# IQ_AMP.net
KiCad netlist of a schematic drawn in Altium Designer
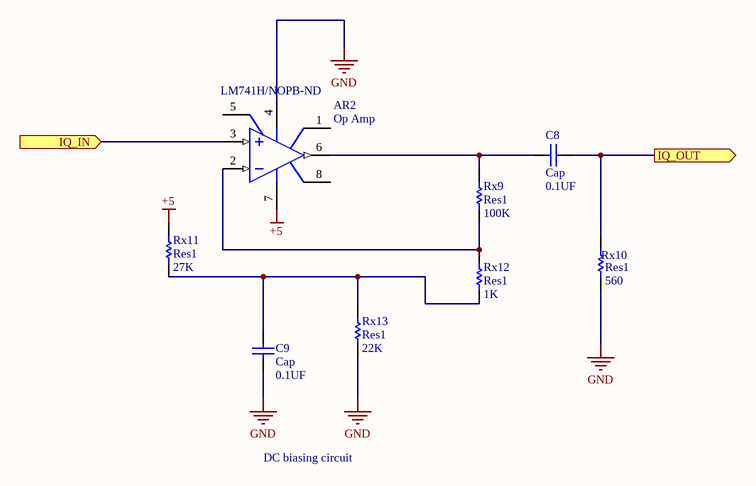
[diagram p0: IQ_AMP.SchDoc]

(export (version "E")
  (design (tool "Eeschema 10.0.6"))
  (components
    (comp (ref "AR2")
      (value "Op Amp")
      (footprint "H-08A")
      (description "FET Operational Amplifier")
      (fields
        (field (name "SUPPLIER PART NUMBER 1") "LM741H/NOPB-ND")
        (field (name "PUBLISHER") "Altium Limited")
      )
      (libsource (lib "Miscellaneous Devices") (part "Op Amp"))
    )
    (comp (ref "C8")
      (value "Cap")
      (footprint "1206")
      (description "Capacitor")
      (fields
        (field (name "ALTIUM_VALUE") "0.1UF")
        (field (name "MANUFACTURER PART NUMBER") "885012208087")
        (field (name "PUBLISHER") "Altium Limited")
      )
      (libsource (lib "ECE295-Capacitors-SMT") (part "CAP CER 0.1UF 50V X7R 1206"))
    )
    (comp (ref "C9")
      (value "Cap")
      (footprint "1206")
      (description "Capacitor")
      (fields
        (field (name "ALTIUM_VALUE") "0.1UF")
        (field (name "MANUFACTURER PART NUMBER") "885012208087")
        (field (name "PUBLISHER") "Altium Limited")
      )
      (libsource (lib "ECE295-Capacitors-SMT") (part "CAP CER 0.1UF 50V X7R 1206"))
    )
    (comp (ref "Rx9")
      (value "Res1")
      (footprint "AXIAL-0.1-RES")
      (description "Resistor")
      (fields
        (field (name "ALTIUM_VALUE") "100K")
        (field (name "MANUFACTURER PART NUMBER") "CFR-25JB-52-100K")
        (field (name "TOLERANCE") "0.05")
        (field (name "PUBLISHER") "Altium Limited")
      )
      (libsource (lib "ECE295-Resistors-TH") (part "RES 100K OHM 5% 1/4W AXIAL"))
    )
    (comp (ref "Rx10")
      (value "Res1")
      (footprint "AXIAL-0.1-RES")
      (description "Resistor")
      (fields
        (field (name "ALTIUM_VALUE") "560")
        (field (name "MANUFACTURER PART NUMBER") "CFR-25JB-52-560R")
        (field (name "TOLERANCE") "0.05")
        (field (name "PUBLISHER") "Altium Limited")
      )
      (libsource (lib "ECE295-Resistors-TH") (part "RES 560 OHM 5% 1/4W AXIAL"))
    )
    (comp (ref "Rx11")
      (value "Res1")
      (footprint "AXIAL-0.1-RES")
      (description "Resistor")
      (fields
        (field (name "ALTIUM_VALUE") "27K")
        (field (name "MANUFACTURER PART NUMBER") "CFR-25JB-52-27K")
        (field (name "TOLERANCE") "0.05")
        (field (name "PUBLISHER") "Altium Limited")
      )
      (libsource (lib "ECE295-Resistors-TH") (part "RES 27K OHM 5% 1/4W AXIAL"))
    )
    (comp (ref "Rx12")
      (value "Res1")
      (footprint "AXIAL-0.1-RES")
      (description "Resistor")
      (fields
        (field (name "MANUFACTURER PART NUMBER") "CFR-25JB-52-1K")
        (field (name "TOLERANCE") "0.05")
        (field (name "ALTIUM_VALUE") "1K")
        (field (name "PUBLISHER") "Altium Limited")
      )
      (libsource (lib "ECE295-Resistors-TH") (part "RES 1K OHM 5% 1/4W AXIAL"))
    )
    (comp (ref "Rx13")
      (value "Res1")
      (footprint "AXIAL-0.1-RES")
      (description "Resistor")
      (fields
        (field (name "ALTIUM_VALUE") "22K")
        (field (name "MANUFACTURER PART NUMBER") "CFR-25JB-52-22K")
        (field (name "TOLERANCE") "0.05")
        (field (name "PUBLISHER") "Altium Limited")
      )
      (libsource (lib "ECE295-Resistors-TH") (part "RES 22K OHM 5% 1/4W AXIAL"))
    )
  )
  (nets
    (net (code "1") (name "+5") (class "Default")
      (node (ref "AR2") (pin "7") (pinfunction "V+_7") (pintype "power_in"))
      (node (ref "Rx11") (pin "2") (pinfunction "2_2") (pintype "passive"))
    )
    (net (code "2") (name "/IQ_IN") (class "Default")
      (node (ref "AR2") (pin "3") (pinfunction "IN+_3") (pintype "input"))
    )
    (net (code "3") (name "/IQ_OUT") (class "Default")
      (node (ref "C8") (pin "2") (pinfunction "2_2") (pintype "passive"))
      (node (ref "Rx10") (pin "2") (pinfunction "2_2") (pintype "passive"))
    )
    (net (code "4") (name "GND") (class "Default")
      (node (ref "AR2") (pin "4") (pinfunction "V-_4") (pintype "power_in"))
      (node (ref "C9") (pin "1") (pinfunction "1_1") (pintype "passive"))
      (node (ref "Rx10") (pin "1") (pinfunction "1_1") (pintype "passive"))
      (node (ref "Rx13") (pin "1") (pinfunction "1_1") (pintype "passive"))
    )
    (net (code "5") (name "Net-(AR2-IN-)") (class "Default")
      (node (ref "AR2") (pin "2") (pinfunction "IN-_2") (pintype "input"))
      (node (ref "Rx12") (pin "2") (pinfunction "2_2") (pintype "passive"))
      (node (ref "Rx9") (pin "1") (pinfunction "1_1") (pintype "passive"))
    )
    (net (code "6") (name "Net-(AR2-OUT)") (class "Default")
      (node (ref "AR2") (pin "6") (pinfunction "OUT_6") (pintype "output"))
      (node (ref "C8") (pin "1") (pinfunction "1_1") (pintype "passive"))
      (node (ref "Rx9") (pin "2") (pinfunction "2_2") (pintype "passive"))
    )
    (net (code "7") (name "Net-(C9-Pad2)") (class "Default")
      (node (ref "C9") (pin "2") (pinfunction "2_2") (pintype "passive"))
      (node (ref "Rx11") (pin "1") (pinfunction "1_1") (pintype "passive"))
      (node (ref "Rx12") (pin "1") (pinfunction "1_1") (pintype "passive"))
      (node (ref "Rx13") (pin "2") (pinfunction "2_2") (pintype "passive"))
    )
    (net (code "8") (name "unconnected-(AR2-OS_NUL-Pad1)") (class "Default")
      (node (ref "AR2") (pin "1") (pinfunction "OS_NUL_1") (pintype "passive"))
    )
    (net (code "9") (name "unconnected-(AR2-OS_NUL-Pad5)") (class "Default")
      (node (ref "AR2") (pin "5") (pinfunction "OS_NUL_5") (pintype "passive"))
    )
    (net (code "10") (name "unconnected-(AR2-TAB-Pad8)") (class "Default")
      (node (ref "AR2") (pin "8") (pinfunction "TAB_8") (pintype "passive"))
    )
  )
)
